# mikro.net
KiCad netlist of a schematic drawn in Altium Designer
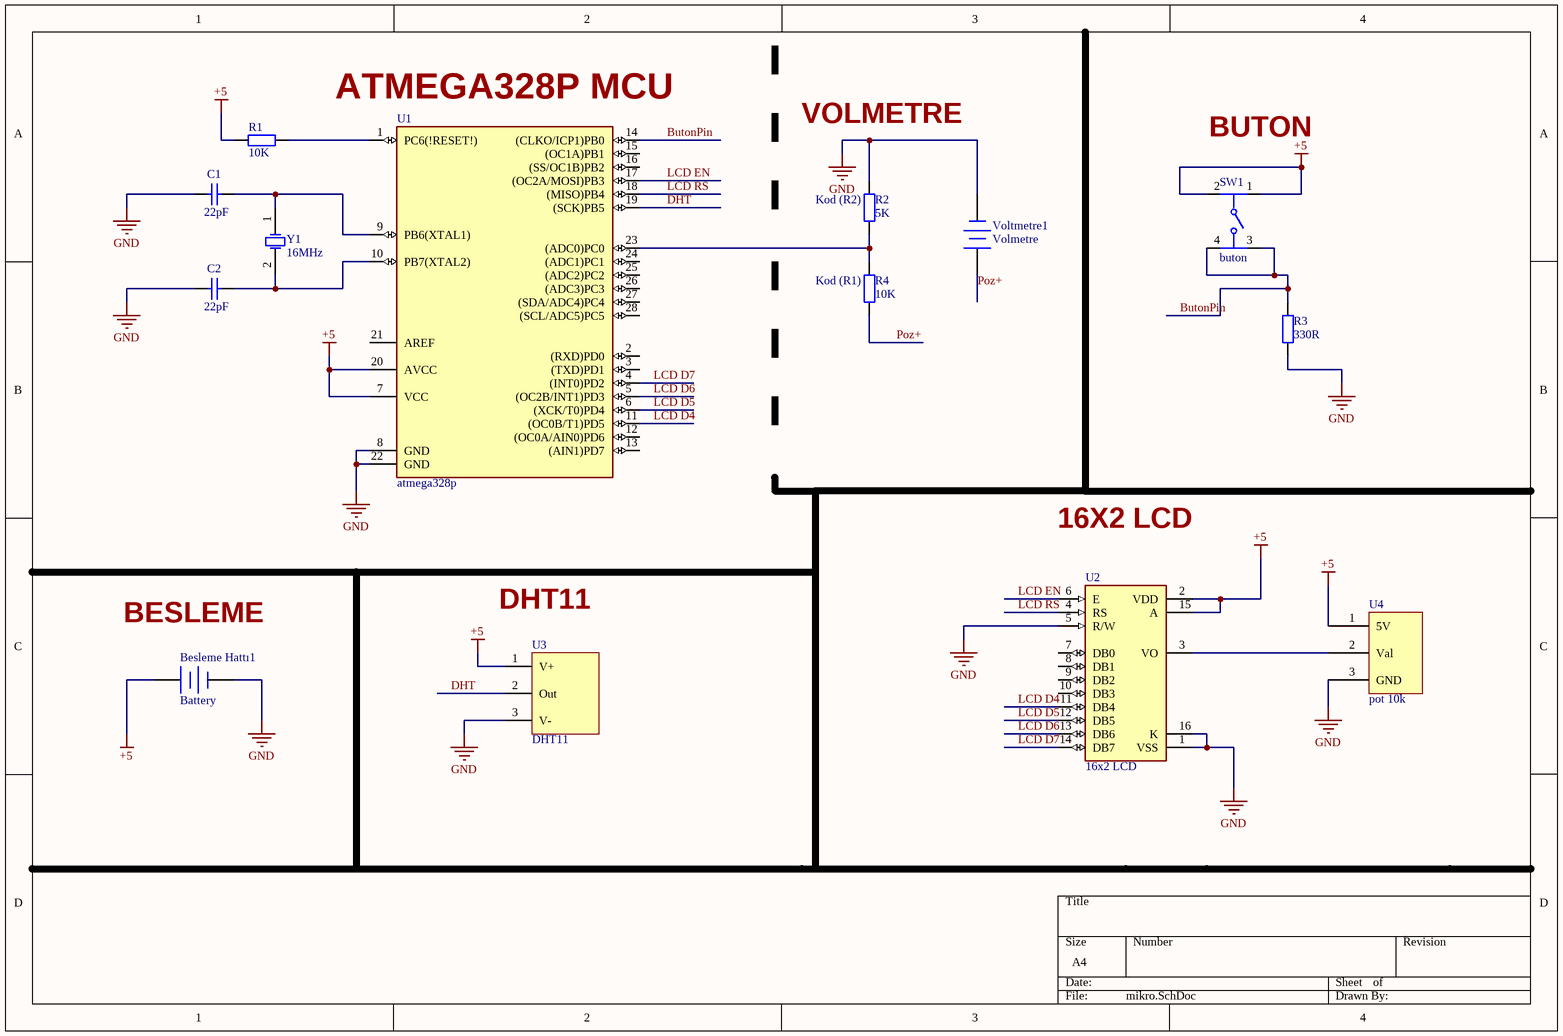
[diagram p0: mikro.SchDoc]

(export (version "E")
  (design (tool "Eeschema 10.0.6"))
  (components
    (comp (ref "Besleme Hattı1")
      (value "Battery")
      (footprint "BAT-2")
      (description "Multicell Battery")
      (fields (field (name "PUBLISHER") "Altium Limited"))
      (libsource (lib "Miscellaneous Devices") (part "Battery"))
    )
    (comp (ref "C1")
      (value "22pF")
      (footprint "RAD-0.3")
      (description "Capacitor")
      (fields (field (name "PUBLISHER") "Altium Limited"))
      (libsource (lib "Miscellaneous Devices") (part "Cap"))
    )
    (comp (ref "C2")
      (value "22pF")
      (footprint "RAD-0.3")
      (description "Capacitor")
      (fields (field (name "PUBLISHER") "Altium Limited"))
      (libsource (lib "Miscellaneous Devices") (part "Cap"))
    )
    (comp (ref "R1")
      (value "10K")
      (footprint "AXIAL-0.4")
      (description "Resistor")
      (fields (field (name "Comment") "res") (field (name "PUBLISHER") "Altium Limited"))
      (libsource (lib "Miscellaneous Devices") (part "Res2"))
    )
    (comp (ref "R2")
      (value "5K")
      (footprint "AXIAL-0.4")
      (description "Resistor")
      (fields (field (name "Comment") "res") (field (name "PUBLISHER") "Altium Limited"))
      (libsource (lib "") (part "Res2_1"))
    )
    (comp (ref "R3")
      (value "330R")
      (footprint "AXIAL-0.4")
      (description "Resistor")
      (fields (field (name "Comment") "res") (field (name "PUBLISHER") "Altium Limited"))
      (libsource (lib "") (part "Res2_1"))
    )
    (comp (ref "R4")
      (value "10K")
      (footprint "AXIAL-0.4")
      (description "Resistor")
      (fields (field (name "Comment") "res") (field (name "PUBLISHER") "Altium Limited"))
      (libsource (lib "") (part "Res2_1"))
    )
    (comp (ref "SW1")
      (value "buton")
      (footprint "FP-1825910-2-0")
      (description "SWITCH TACTILE SPST-NO 0.05A 24V")
      (fields
        (field (name "OCTOPART") "https://octopart.com/1825910-2-te+connectivity-42270502")
        (field (name "MANUFACTURER") "TE")
      )
      (libsource (lib "Altium Content Vault") (part "b8895f3f4cefb76e1819d2863dba89b"))
    )
    (comp (ref "U1")
      (value "atmega328p")
      (footprint "atmega328p")
      (libsource (lib "mikro") (part "Atmega328p"))
    )
    (comp (ref "U2") (value "16x2 LCD") (footprint "16x2 LCD") (libsource (lib "mikro") (part "16x2 LCD")))
    (comp (ref "U3") (value "DHT11") (footprint "DHT11") (libsource (lib "mikro") (part "DHT11")))
    (comp (ref "U4") (value "pot 10k") (footprint "pot 10k") (libsource (lib "mikro") (part "pot 10k")))
    (comp (ref "Voltmetre1")
      (value "Volmetre")
      (footprint "BAT-2")
      (description "Volmetre ucları")
      (fields (field (name "PUBLISHER") "Altium Limited"))
      (libsource (lib "Miscellaneous Devices") (part "Battery"))
    )
    (comp (ref "Y1")
      (value "16MHz")
      (footprint "R38")
      (description "16MHZ Crystal Oscillator")
      (fields (field (name "PUBLISHER") "Altium Limited"))
      (libsource (lib "Miscellaneous Devices") (part "XTAL"))
    )
  )
  (nets
    (net (code "1") (name "+5") (class "Default")
      (node (ref "Besleme Hattı1") (pin "1") (pinfunction "+_1") (pintype "passive"))
      (node (ref "R1") (pin "1") (pinfunction "1_1") (pintype "passive"))
      (node (ref "SW1") (pin "1") (pinfunction "1_1") (pintype "passive"))
      (node (ref "SW1") (pin "2") (pinfunction "2_2") (pintype "passive"))
      (node (ref "U1") (pin "20") (pinfunction "AVCC_20") (pintype "power_in"))
      (node (ref "U1") (pin "7") (pinfunction "VCC_7") (pintype "power_in"))
      (node (ref "U2") (pin "15") (pinfunction "A_15") (pintype "passive"))
      (node (ref "U2") (pin "2") (pinfunction "VDD_2") (pintype "power_in"))
      (node (ref "U3") (pin "1") (pinfunction "V+_1") (pintype "passive"))
      (node (ref "U4") (pin "1") (pinfunction "5V_1") (pintype "passive"))
    )
    (net (code "2") (name "/ButonPin") (class "Default")
      (node (ref "R3") (pin "2") (pinfunction "2_2") (pintype "passive"))
      (node (ref "SW1") (pin "3") (pinfunction "3_3") (pintype "passive"))
      (node (ref "SW1") (pin "4") (pinfunction "4_4") (pintype "passive"))
      (node (ref "U1") (pin "14") (pinfunction "(CLKO/ICP1)PB0_14") (pintype "bidirectional"))
    )
    (net (code "3") (name "/DHT") (class "Default")
      (node (ref "U1") (pin "19") (pinfunction "(SCK)PB5_19") (pintype "bidirectional"))
      (node (ref "U3") (pin "2") (pinfunction "Out_2") (pintype "passive"))
    )
    (net (code "4") (name "/LCD D4") (class "Default")
      (node (ref "U1") (pin "11") (pinfunction "(OC0B/T1)PD5_11") (pintype "bidirectional"))
      (node (ref "U2") (pin "11") (pinfunction "DB4_11") (pintype "bidirectional"))
    )
    (net (code "5") (name "/LCD D5") (class "Default")
      (node (ref "U1") (pin "6") (pinfunction "(XCK/T0)PD4_6") (pintype "bidirectional"))
      (node (ref "U2") (pin "12") (pinfunction "DB5_12") (pintype "bidirectional"))
    )
    (net (code "6") (name "/LCD D6") (class "Default")
      (node (ref "U1") (pin "5") (pinfunction "(OC2B/INT1)PD3_5") (pintype "bidirectional"))
      (node (ref "U2") (pin "13") (pinfunction "DB6_13") (pintype "bidirectional"))
    )
    (net (code "7") (name "/LCD D7") (class "Default")
      (node (ref "U1") (pin "4") (pinfunction "(INT0)PD2_4") (pintype "bidirectional"))
      (node (ref "U2") (pin "14") (pinfunction "DB7_14") (pintype "bidirectional"))
    )
    (net (code "8") (name "/LCD EN") (class "Default")
      (node (ref "U1") (pin "17") (pinfunction "(OC2A/MOSI)PB3_17") (pintype "bidirectional"))
      (node (ref "U2") (pin "6") (pinfunction "E_6") (pintype "input"))
    )
    (net (code "9") (name "/LCD RS") (class "Default")
      (node (ref "U1") (pin "18") (pinfunction "(MISO)PB4_18") (pintype "bidirectional"))
      (node (ref "U2") (pin "4") (pinfunction "RS_4") (pintype "input"))
    )
    (net (code "10") (name "/Poz+") (class "Default")
      (node (ref "R4") (pin "1") (pinfunction "1_1") (pintype "passive"))
      (node (ref "Voltmetre1") (pin "1") (pinfunction "+_1") (pintype "passive"))
    )
    (net (code "11") (name "GND") (class "Default")
      (node (ref "Besleme Hattı1") (pin "2") (pinfunction "-_2") (pintype "passive"))
      (node (ref "C1") (pin "1") (pinfunction "1_1") (pintype "passive"))
      (node (ref "C2") (pin "1") (pinfunction "1_1") (pintype "passive"))
      (node (ref "R2") (pin "2") (pinfunction "2_2") (pintype "passive"))
      (node (ref "R3") (pin "1") (pinfunction "1_1") (pintype "passive"))
      (node (ref "U1") (pin "22") (pinfunction "GND_22") (pintype "power_in"))
      (node (ref "U1") (pin "8") (pinfunction "GND_8") (pintype "power_in"))
      (node (ref "U2") (pin "1") (pinfunction "VSS_1") (pintype "power_in"))
      (node (ref "U2") (pin "16") (pinfunction "K_16") (pintype "passive"))
      (node (ref "U2") (pin "5") (pinfunction "R/W_5") (pintype "input"))
      (node (ref "U3") (pin "3") (pinfunction "V-_3") (pintype "passive"))
      (node (ref "U4") (pin "3") (pinfunction "GND_3") (pintype "passive"))
      (node (ref "Voltmetre1") (pin "2") (pinfunction "-_2") (pintype "passive"))
    )
    (net (code "12") (name "Net-(U1-(ADC0)PC0)") (class "Default")
      (node (ref "R2") (pin "1") (pinfunction "1_1") (pintype "passive"))
      (node (ref "R4") (pin "2") (pinfunction "2_2") (pintype "passive"))
      (node (ref "U1") (pin "23") (pinfunction "(ADC0)PC0_23") (pintype "bidirectional"))
    )
    (net (code "13") (name "Net-(U1-PB6(XTAL1))") (class "Default")
      (node (ref "C1") (pin "2") (pinfunction "2_2") (pintype "passive"))
      (node (ref "U1") (pin "9") (pinfunction "PB6(XTAL1)_9") (pintype "bidirectional"))
      (node (ref "Y1") (pin "1") (pinfunction "OSC1_1") (pintype "passive"))
    )
    (net (code "14") (name "Net-(U1-PB7(XTAL2))") (class "Default")
      (node (ref "C2") (pin "2") (pinfunction "2_2") (pintype "passive"))
      (node (ref "U1") (pin "10") (pinfunction "PB7(XTAL2)_10") (pintype "bidirectional"))
      (node (ref "Y1") (pin "2") (pinfunction "OSC2_2") (pintype "passive"))
    )
    (net (code "15") (name "Net-(U1-PC6(!RESET!))") (class "Default")
      (node (ref "R1") (pin "2") (pinfunction "2_2") (pintype "passive"))
      (node (ref "U1") (pin "1") (pinfunction "PC6(!RESET!)_1") (pintype "bidirectional"))
    )
    (net (code "16") (name "Net-(U2-VO)") (class "Default")
      (node (ref "U2") (pin "3") (pinfunction "VO_3") (pintype "power_in"))
      (node (ref "U4") (pin "2") (pinfunction "Val_2") (pintype "passive"))
    )
    (net (code "17") (name "unconnected-(U1-(ADC1)PC1-Pad24)") (class "Default")
      (node (ref "U1") (pin "24") (pinfunction "(ADC1)PC1_24") (pintype "bidirectional"))
    )
    (net (code "18") (name "unconnected-(U1-(ADC2)PC2-Pad25)") (class "Default")
      (node (ref "U1") (pin "25") (pinfunction "(ADC2)PC2_25") (pintype "bidirectional"))
    )
    (net (code "19") (name "unconnected-(U1-(ADC3)PC3-Pad26)") (class "Default")
      (node (ref "U1") (pin "26") (pinfunction "(ADC3)PC3_26") (pintype "bidirectional"))
    )
    (net (code "20") (name "unconnected-(U1-(AIN1)PD7-Pad13)") (class "Default")
      (node (ref "U1") (pin "13") (pinfunction "(AIN1)PD7_13") (pintype "bidirectional"))
    )
    (net (code "21") (name "unconnected-(U1-(OC0A{slash}AIN0)PD6-Pad12)") (class "Default")
      (node (ref "U1") (pin "12") (pinfunction "(OC0A/AIN0)PD6_12") (pintype "bidirectional"))
    )
    (net (code "22") (name "unconnected-(U1-(OC1A)PB1-Pad15)") (class "Default")
      (node (ref "U1") (pin "15") (pinfunction "(OC1A)PB1_15") (pintype "bidirectional"))
    )
    (net (code "23") (name "unconnected-(U1-(RXD)PD0-Pad2)") (class "Default")
      (node (ref "U1") (pin "2") (pinfunction "(RXD)PD0_2") (pintype "bidirectional"))
    )
    (net (code "24") (name "unconnected-(U1-(SCL{slash}ADC5)PC5-Pad28)") (class "Default")
      (node (ref "U1") (pin "28") (pinfunction "(SCL/ADC5)PC5_28") (pintype "bidirectional"))
    )
    (net (code "25") (name "unconnected-(U1-(SDA{slash}ADC4)PC4-Pad27)") (class "Default")
      (node (ref "U1") (pin "27") (pinfunction "(SDA/ADC4)PC4_27") (pintype "bidirectional"))
    )
    (net (code "26") (name "unconnected-(U1-(SS{slash}OC1B)PB2-Pad16)") (class "Default")
      (node (ref "U1") (pin "16") (pinfunction "(SS/OC1B)PB2_16") (pintype "bidirectional"))
    )
    (net (code "27") (name "unconnected-(U1-(TXD)PD1-Pad3)") (class "Default")
      (node (ref "U1") (pin "3") (pinfunction "(TXD)PD1_3") (pintype "bidirectional"))
    )
    (net (code "28") (name "unconnected-(U1-AREF-Pad21)") (class "Default")
      (node (ref "U1") (pin "21") (pinfunction "AREF_21") (pintype "passive"))
    )
    (net (code "29") (name "unconnected-(U2-DB0-Pad7)") (class "Default")
      (node (ref "U2") (pin "7") (pinfunction "DB0_7") (pintype "bidirectional"))
    )
    (net (code "30") (name "unconnected-(U2-DB1-Pad8)") (class "Default")
      (node (ref "U2") (pin "8") (pinfunction "DB1_8") (pintype "bidirectional"))
    )
    (net (code "31") (name "unconnected-(U2-DB2-Pad9)") (class "Default")
      (node (ref "U2") (pin "9") (pinfunction "DB2_9") (pintype "bidirectional"))
    )
    (net (code "32") (name "unconnected-(U2-DB3-Pad10)") (class "Default")
      (node (ref "U2") (pin "10") (pinfunction "DB3_10") (pintype "bidirectional"))
    )
  )
)
